# mapleSDuino-V0_1_010-eagle7.net
KiCad netlist of a schematic drawn in EAGLE
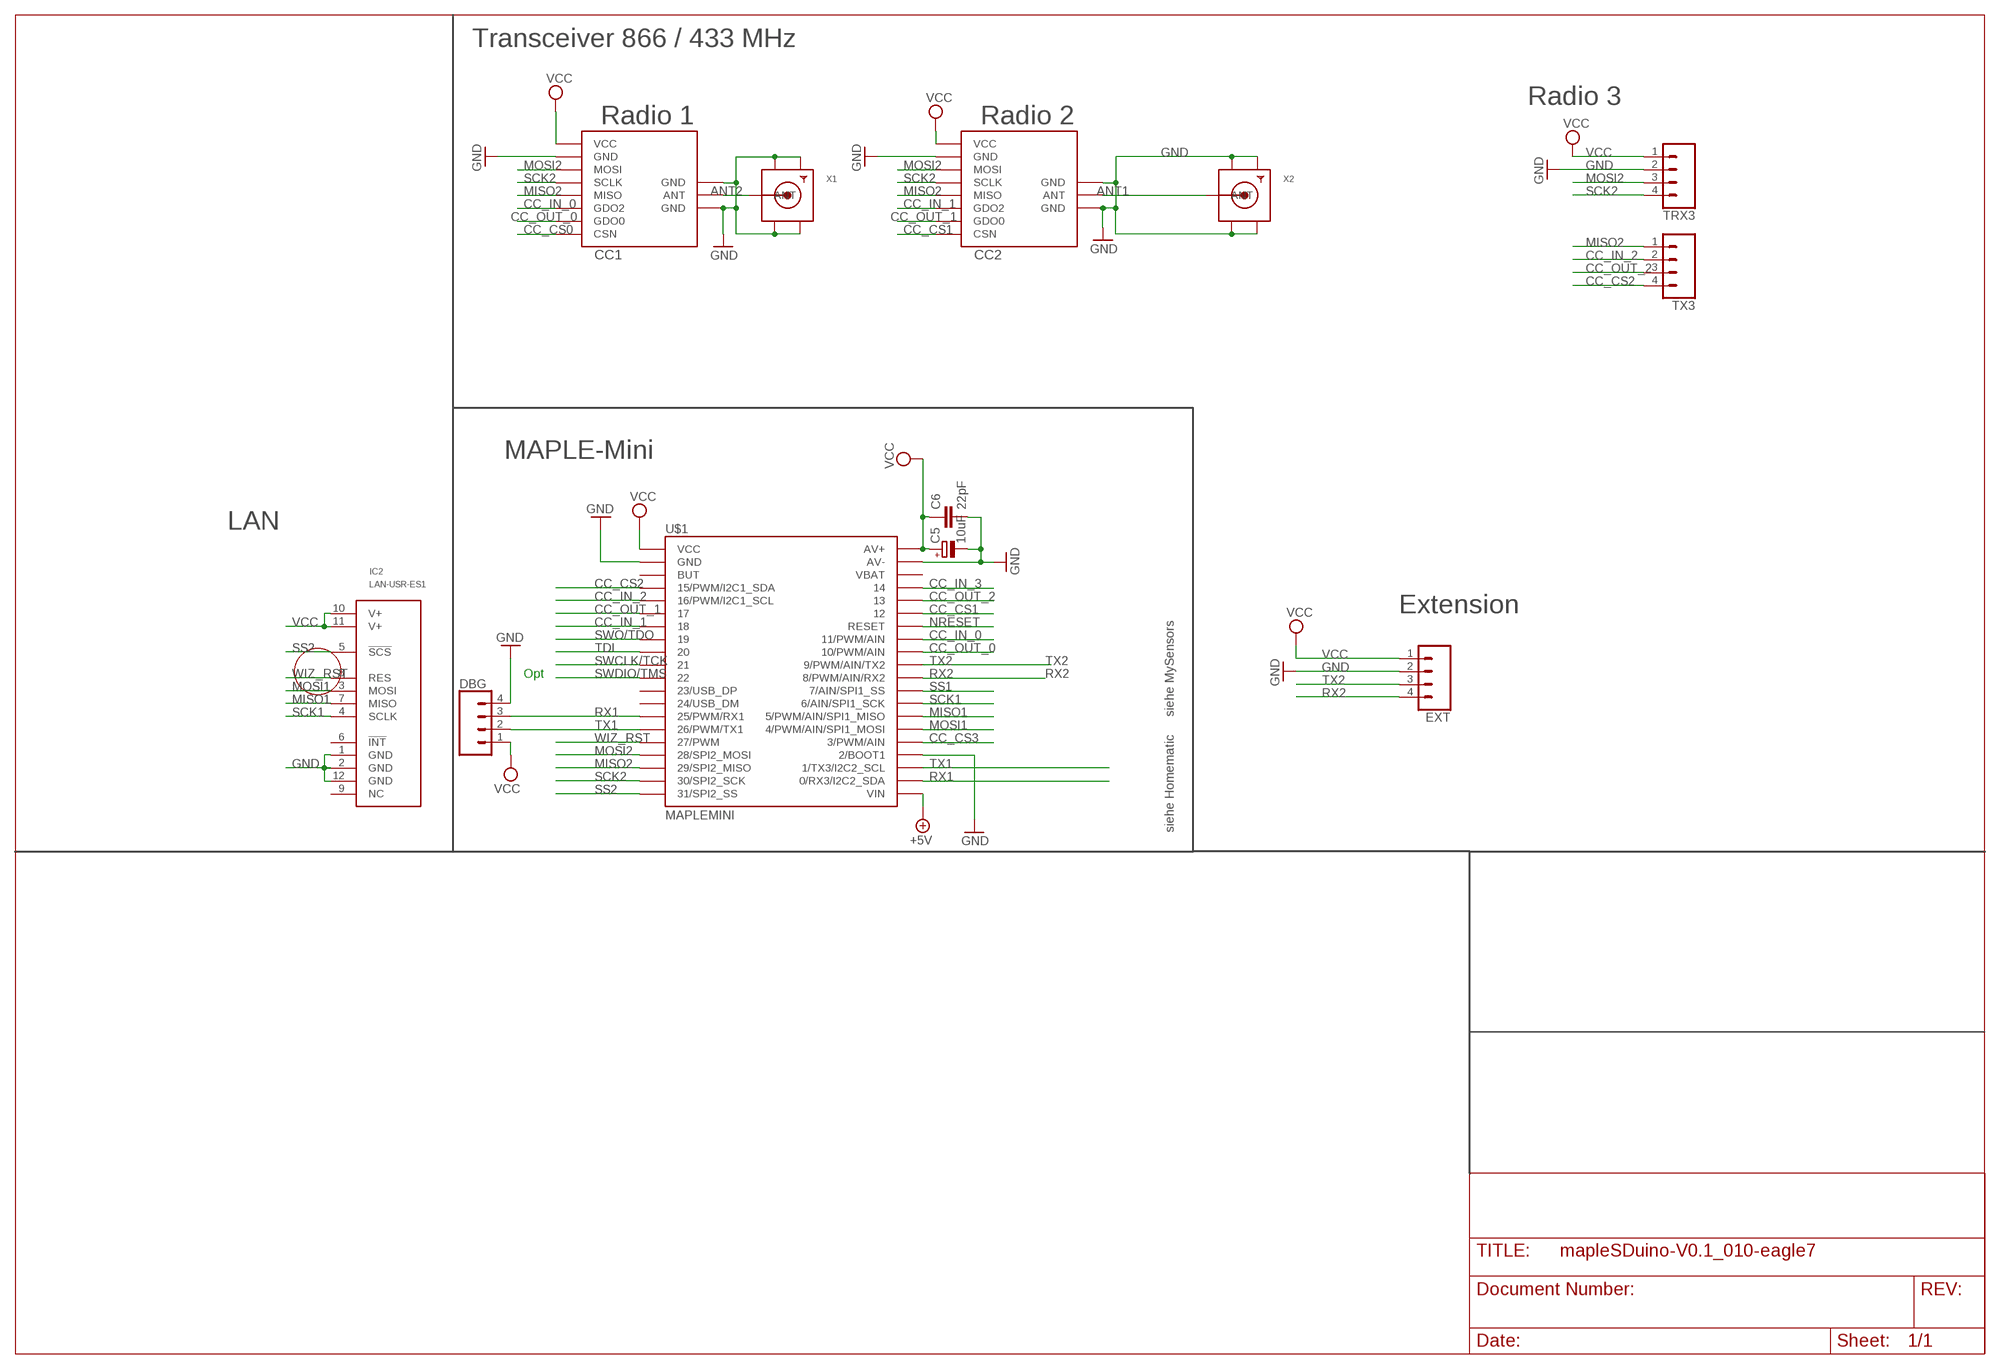
[diagram p0: schematic, sheet 1]

(export (version "E")
  (design (tool "Eeschema 10.0.6"))
  (components
    (comp (ref "C5")
      (value "10uF")
      (footprint "eagle-import:R_2012-12W")
      (libsource (lib "eagle-import") (part "CPOL-EUR/2012-12W"))
    )
    (comp (ref "C6")
      (value "22pF")
      (footprint "eagle-import:C0805")
      (libsource (lib "eagle-import") (part "C-EUC0805"))
    )
    (comp (ref "CC1")
      (value "CC1101")
      (footprint "eagle-import:CC1101_MODULE1_SMD")
      (libsource (lib "eagle-import") (part "CC1101_MODULE1SMD"))
    )
    (comp (ref "CC2")
      (value "CC1101_MODULE1SMD")
      (footprint "eagle-import:CC1101_MODULE1_SMD")
      (libsource (lib "eagle-import") (part "CC1101_MODULE1SMD"))
    )
    (comp (ref "DBG")
      (value "CONN_04LOCK")
      (footprint "eagle-import:1X04_LOCK")
      (libsource (lib "eagle-import") (part "CONN_04LOCK"))
    )
    (comp (ref "EXT")
      (value "CONN_04PTH")
      (footprint "eagle-import:1X04")
      (libsource (lib "eagle-import") (part "CONN_04PTH"))
    )
    (comp (ref "IC2")
      (value "LAN-USR-ES1")
      (footprint "eagle-import:USR-ES1")
      (libsource (lib "eagle-import") (part "LAN-USR-ES1"))
    )
    (comp (ref "TRX3")
      (value "CONN_04PTH")
      (footprint "eagle-import:1X04")
      (libsource (lib "eagle-import") (part "CONN_04PTH"))
    )
    (comp (ref "TX3")
      (value "CONN_04PTH")
      (footprint "eagle-import:1X04")
      (libsource (lib "eagle-import") (part "CONN_04PTH"))
    )
    (comp (ref "U$1")
      (value "MAPLEMINI")
      (footprint "eagle-import:20-DIP")
      (libsource (lib "eagle-import") (part "MAPLEMINI"))
    )
    (comp (ref "X1")
      (value "SMACONNECTOR_EDGE")
      (footprint "eagle-import:SMA_EDGELAUNCH")
      (libsource (lib "eagle-import") (part "SMACONNECTOR_EDGE"))
    )
    (comp (ref "X2")
      (value "SMACONNECTOR_EDGE")
      (footprint "eagle-import:SMA_EDGELAUNCH")
      (libsource (lib "eagle-import") (part "SMACONNECTOR_EDGE"))
    )
  )
  (nets
    (net (code "1") (name "+5V") (class "Default")
      (node (ref "U$1") (pin "21") (pinfunction "VIN_21") (pintype "bidirectional"))
    )
    (net (code "2") (name "/ANT1") (class "Default")
      (node (ref "CC2") (pin "ANT") (pinfunction "ANT_ANT") (pintype "output"))
      (node (ref "X2") (pin "P") (pinfunction "ANT_P") (pintype "bidirectional"))
    )
    (net (code "3") (name "/ANT2") (class "Default")
      (node (ref "CC1") (pin "ANT") (pinfunction "ANT_ANT") (pintype "output"))
      (node (ref "X1") (pin "P") (pinfunction "ANT_P") (pintype "bidirectional"))
    )
    (net (code "4") (name "/CC_CS0") (class "Default")
      (node (ref "CC1") (pin "CSN") (pinfunction "CSN_CSN") (pintype "bidirectional"))
    )
    (net (code "5") (name "/CC_CS1") (class "Default")
      (node (ref "CC2") (pin "CSN") (pinfunction "CSN_CSN") (pintype "bidirectional"))
      (node (ref "U$1") (pin "35") (pinfunction "12_35") (pintype "bidirectional"))
    )
    (net (code "6") (name "/CC_CS2") (class "Default")
      (node (ref "TX3") (pin "4") (pinfunction "4_4") (pintype "passive"))
      (node (ref "U$1") (pin "4") (pinfunction "15/PWM/I2C1_SDA_4") (pintype "bidirectional"))
    )
    (net (code "7") (name "/CC_CS3") (class "Default")
      (node (ref "U$1") (pin "25") (pinfunction "3/PWM/AIN_25") (pintype "bidirectional"))
    )
    (net (code "8") (name "/CC_IN_0") (class "Default")
      (node (ref "CC1") (pin "GDO2") (pinfunction "GDO2_GDO2") (pintype "bidirectional"))
      (node (ref "U$1") (pin "33") (pinfunction "11/PWM/AIN_33") (pintype "bidirectional"))
    )
    (net (code "9") (name "/CC_IN_1") (class "Default")
      (node (ref "CC2") (pin "GDO2") (pinfunction "GDO2_GDO2") (pintype "bidirectional"))
      (node (ref "U$1") (pin "7") (pinfunction "18_7") (pintype "bidirectional"))
    )
    (net (code "10") (name "/CC_IN_2") (class "Default")
      (node (ref "TX3") (pin "2") (pinfunction "2_2") (pintype "passive"))
      (node (ref "U$1") (pin "5") (pinfunction "16/PWM/I2C1_SCL_5") (pintype "bidirectional"))
    )
    (net (code "11") (name "/CC_IN_3") (class "Default")
      (node (ref "U$1") (pin "37") (pinfunction "14_37") (pintype "bidirectional"))
    )
    (net (code "12") (name "/CC_OUT_0") (class "Default")
      (node (ref "CC1") (pin "GDO0") (pinfunction "GDO0_GDO0") (pintype "bidirectional"))
      (node (ref "U$1") (pin "32") (pinfunction "10/PWM/AIN_32") (pintype "bidirectional"))
    )
    (net (code "13") (name "/CC_OUT_1") (class "Default")
      (node (ref "CC2") (pin "GDO0") (pinfunction "GDO0_GDO0") (pintype "bidirectional"))
      (node (ref "U$1") (pin "6") (pinfunction "17_6") (pintype "bidirectional"))
    )
    (net (code "14") (name "/CC_OUT_2") (class "Default")
      (node (ref "TX3") (pin "3") (pinfunction "3_3") (pintype "passive"))
      (node (ref "U$1") (pin "36") (pinfunction "13_36") (pintype "bidirectional"))
    )
    (net (code "15") (name "/MISO1") (class "Default")
      (node (ref "IC2") (pin "7") (pinfunction "MISO_7") (pintype "bidirectional"))
      (node (ref "U$1") (pin "27") (pinfunction "5/PWM/AIN/SPI1_MISO_27") (pintype "bidirectional"))
    )
    (net (code "16") (name "/MISO2") (class "Default")
      (node (ref "CC1") (pin "MISO") (pinfunction "MISO_MISO") (pintype "bidirectional"))
      (node (ref "CC2") (pin "MISO") (pinfunction "MISO_MISO") (pintype "bidirectional"))
      (node (ref "TX3") (pin "1") (pinfunction "1_1") (pintype "passive"))
      (node (ref "U$1") (pin "18") (pinfunction "29/SPI2_MISO_18") (pintype "bidirectional"))
    )
    (net (code "17") (name "/MOSI1") (class "Default")
      (node (ref "IC2") (pin "3") (pinfunction "MOSI_3") (pintype "bidirectional"))
      (node (ref "U$1") (pin "26") (pinfunction "4/PWM/AIN/SPI1_MOSI_26") (pintype "bidirectional"))
    )
    (net (code "18") (name "/MOSI2") (class "Default")
      (node (ref "CC1") (pin "MOSI") (pinfunction "MOSI_MOSI") (pintype "bidirectional"))
      (node (ref "CC2") (pin "MOSI") (pinfunction "MOSI_MOSI") (pintype "bidirectional"))
      (node (ref "TRX3") (pin "3") (pinfunction "3_3") (pintype "passive"))
      (node (ref "U$1") (pin "17") (pinfunction "28/SPI2_MOSI_17") (pintype "bidirectional"))
    )
    (net (code "19") (name "/NRESET") (class "Default")
      (node (ref "U$1") (pin "34") (pinfunction "RESET_34") (pintype "bidirectional"))
    )
    (net (code "20") (name "/RX1") (class "Default")
      (node (ref "DBG") (pin "3") (pinfunction "3_3") (pintype "passive"))
      (node (ref "U$1") (pin "14") (pinfunction "25/PWM/RX1_14") (pintype "bidirectional"))
      (node (ref "U$1") (pin "22") (pinfunction "0/RX3/I2C2_SDA_22") (pintype "bidirectional"))
    )
    (net (code "21") (name "/RX2") (class "Default")
      (node (ref "EXT") (pin "4") (pinfunction "4_4") (pintype "passive"))
      (node (ref "U$1") (pin "30") (pinfunction "8/PWM/AIN/RX2_30") (pintype "bidirectional"))
    )
    (net (code "22") (name "/SCK1") (class "Default")
      (node (ref "IC2") (pin "4") (pinfunction "SCLK_4") (pintype "input"))
      (node (ref "U$1") (pin "28") (pinfunction "6/AIN/SPI1_SCK_28") (pintype "bidirectional"))
    )
    (net (code "23") (name "/SCK2") (class "Default")
      (node (ref "CC1") (pin "SCLK") (pinfunction "SCLK_SCLK") (pintype "bidirectional"))
      (node (ref "CC2") (pin "SCLK") (pinfunction "SCLK_SCLK") (pintype "bidirectional"))
      (node (ref "TRX3") (pin "4") (pinfunction "4_4") (pintype "passive"))
      (node (ref "U$1") (pin "19") (pinfunction "30/SPI2_SCK_19") (pintype "bidirectional"))
    )
    (net (code "24") (name "/SS1") (class "Default")
      (node (ref "U$1") (pin "29") (pinfunction "7/AIN/SPI1_SS_29") (pintype "bidirectional"))
    )
    (net (code "25") (name "/SS2") (class "Default")
      (node (ref "IC2") (pin "5") (pinfunction "~{SCS}_5") (pintype "input"))
      (node (ref "U$1") (pin "20") (pinfunction "31/SPI2_SS_20") (pintype "bidirectional"))
    )
    (net (code "26") (name "/SWCLK{slash}TCK") (class "Default")
      (node (ref "U$1") (pin "10") (pinfunction "21_10") (pintype "bidirectional"))
    )
    (net (code "27") (name "/SWDIO{slash}TMS") (class "Default")
      (node (ref "U$1") (pin "11") (pinfunction "22_11") (pintype "bidirectional"))
    )
    (net (code "28") (name "/SWO{slash}TDO") (class "Default")
      (node (ref "U$1") (pin "8") (pinfunction "19_8") (pintype "bidirectional"))
    )
    (net (code "29") (name "/TDI") (class "Default")
      (node (ref "U$1") (pin "9") (pinfunction "20_9") (pintype "bidirectional"))
    )
    (net (code "30") (name "/TX1") (class "Default")
      (node (ref "DBG") (pin "2") (pinfunction "2_2") (pintype "passive"))
      (node (ref "U$1") (pin "15") (pinfunction "26/PWM/TX1_15") (pintype "bidirectional"))
      (node (ref "U$1") (pin "23") (pinfunction "1/TX3/I2C2_SCL_23") (pintype "bidirectional"))
    )
    (net (code "31") (name "/TX2") (class "Default")
      (node (ref "EXT") (pin "3") (pinfunction "3_3") (pintype "passive"))
      (node (ref "U$1") (pin "31") (pinfunction "9/PWM/AIN/TX2_31") (pintype "bidirectional"))
    )
    (net (code "32") (name "/WIZ_RST") (class "Default")
      (node (ref "IC2") (pin "8") (pinfunction "RES_8") (pintype "input"))
      (node (ref "U$1") (pin "16") (pinfunction "27/PWM_16") (pintype "bidirectional"))
    )
    (net (code "33") (name "GND") (class "Default")
      (node (ref "C5") (pin "-") (pinfunction "-_-") (pintype "passive"))
      (node (ref "C6") (pin "2") (pinfunction "2_2") (pintype "passive"))
      (node (ref "CC1") (pin "GND@0") (pinfunction "GND_GND@0") (pintype "power_in"))
      (node (ref "CC1") (pin "GND@1") (pinfunction "GND_GND@1") (pintype "power_in"))
      (node (ref "CC1") (pin "GND@2") (pinfunction "GND_GND@2") (pintype "power_in"))
      (node (ref "CC2") (pin "GND@0") (pinfunction "GND_GND@0") (pintype "power_in"))
      (node (ref "CC2") (pin "GND@1") (pinfunction "GND_GND@1") (pintype "power_in"))
      (node (ref "CC2") (pin "GND@2") (pinfunction "GND_GND@2") (pintype "power_in"))
      (node (ref "DBG") (pin "4") (pinfunction "4_4") (pintype "passive"))
      (node (ref "EXT") (pin "2") (pinfunction "2_2") (pintype "passive"))
      (node (ref "IC2") (pin "1") (pinfunction "GND_1") (pintype "power_in"))
      (node (ref "IC2") (pin "12") (pinfunction "GND_12") (pintype "power_in"))
      (node (ref "IC2") (pin "2") (pinfunction "GND_2") (pintype "power_in"))
      (node (ref "TRX3") (pin "2") (pinfunction "2_2") (pintype "passive"))
      (node (ref "U$1") (pin "2") (pinfunction "GND_2") (pintype "bidirectional"))
      (node (ref "U$1") (pin "24") (pinfunction "2/BOOT1_24") (pintype "bidirectional"))
      (node (ref "U$1") (pin "39") (pinfunction "AV-_39") (pintype "bidirectional"))
      (node (ref "X1") (pin "GND@1") (pinfunction "GND4_GND@1") (pintype "power_in"))
      (node (ref "X1") (pin "GND@2") (pinfunction "GND3_GND@2") (pintype "power_in"))
      (node (ref "X1") (pin "GND@3") (pinfunction "GND2_GND@3") (pintype "power_in"))
      (node (ref "X1") (pin "GND@4") (pinfunction "GND1_GND@4") (pintype "power_in"))
      (node (ref "X2") (pin "GND@1") (pinfunction "GND4_GND@1") (pintype "power_in"))
      (node (ref "X2") (pin "GND@2") (pinfunction "GND3_GND@2") (pintype "power_in"))
      (node (ref "X2") (pin "GND@3") (pinfunction "GND2_GND@3") (pintype "power_in"))
      (node (ref "X2") (pin "GND@4") (pinfunction "GND1_GND@4") (pintype "power_in"))
    )
    (net (code "34") (name "VCC") (class "Default")
      (node (ref "C5") (pin "+") (pinfunction "+_+") (pintype "passive"))
      (node (ref "C6") (pin "1") (pinfunction "1_1") (pintype "passive"))
      (node (ref "CC1") (pin "VCC") (pinfunction "VCC_VCC") (pintype "power_in"))
      (node (ref "CC2") (pin "VCC") (pinfunction "VCC_VCC") (pintype "power_in"))
      (node (ref "DBG") (pin "1") (pinfunction "1_1") (pintype "passive"))
      (node (ref "EXT") (pin "1") (pinfunction "1_1") (pintype "passive"))
      (node (ref "IC2") (pin "10") (pinfunction "V+_10") (pintype "power_in"))
      (node (ref "IC2") (pin "11") (pinfunction "V+_11") (pintype "power_in"))
      (node (ref "TRX3") (pin "1") (pinfunction "1_1") (pintype "passive"))
      (node (ref "U$1") (pin "1") (pinfunction "VCC_1") (pintype "bidirectional"))
      (node (ref "U$1") (pin "40") (pinfunction "AV+_40") (pintype "bidirectional"))
    )
    (net (code "35") (name "unconnected-(IC2-NC-Pad9)") (class "Default")
      (node (ref "IC2") (pin "9") (pinfunction "NC_9") (pintype "no_connect"))
    )
    (net (code "36") (name "unconnected-(IC2-~{INT}-Pad6)") (class "Default")
      (node (ref "IC2") (pin "6") (pinfunction "~{INT}_6") (pintype "output"))
    )
    (net (code "37") (name "unconnected-(U$1-23{slash}USB_DP-Pad12)") (class "Default")
      (node (ref "U$1") (pin "12") (pinfunction "23/USB_DP_12") (pintype "bidirectional"))
    )
    (net (code "38") (name "unconnected-(U$1-24{slash}USB_DM-Pad13)") (class "Default")
      (node (ref "U$1") (pin "13") (pinfunction "24/USB_DM_13") (pintype "bidirectional"))
    )
    (net (code "39") (name "unconnected-(U$1-BUT-Pad3)") (class "Default")
      (node (ref "U$1") (pin "3") (pinfunction "BUT_3") (pintype "bidirectional"))
    )
    (net (code "40") (name "unconnected-(U$1-VBAT-Pad38)") (class "Default")
      (node (ref "U$1") (pin "38") (pinfunction "VBAT_38") (pintype "bidirectional"))
    )
  )
)
